# 4_viper_eagle_rep-periferals.net
KiCad netlist of a schematic drawn in Altium Designer
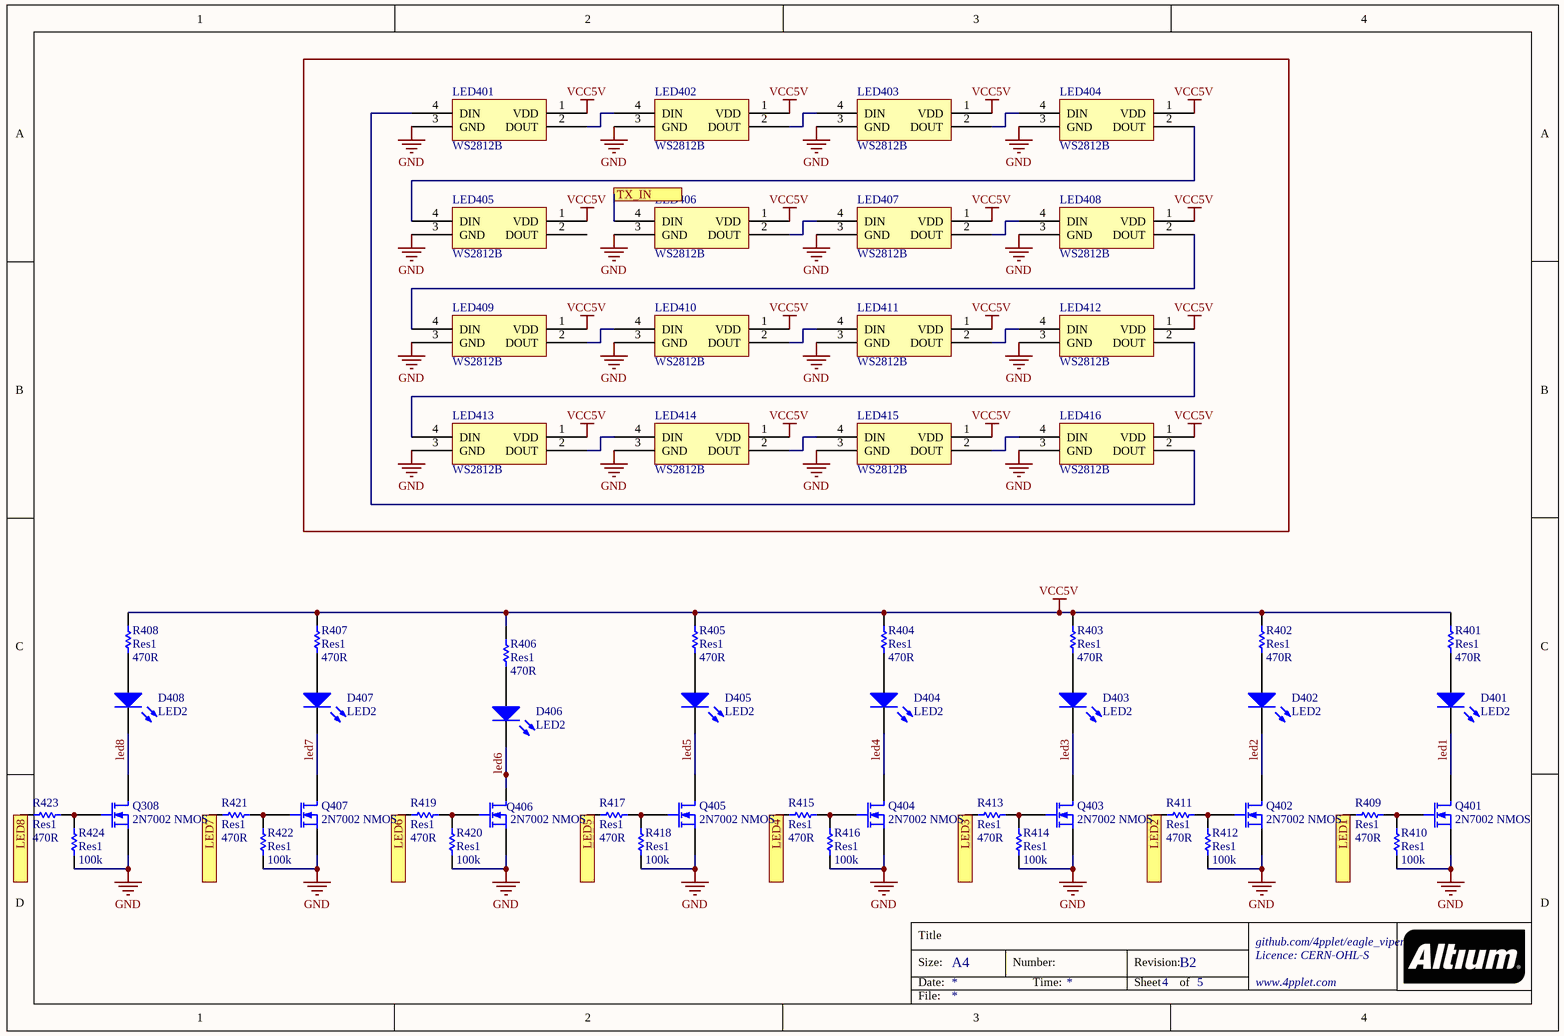
[diagram p0: 4_viper_eagle_rep-periferals.SchDoc]

(export (version "E")
  (design (tool "Eeschema 10.0.6"))
  (components
    (comp (ref "D401")
      (value "LED2")
      (footprint "LED - THT")
      (description "Typical RED, GREEN, YELLOW, AMBER GaAs LED")
      (libsource (lib "Miscellaneous Devices") (part "LED2"))
    )
    (comp (ref "D402")
      (value "LED2")
      (footprint "LED - THT")
      (description "Typical RED, GREEN, YELLOW, AMBER GaAs LED")
      (libsource (lib "Miscellaneous Devices") (part "LED2"))
    )
    (comp (ref "D403")
      (value "LED2")
      (footprint "LED - THT")
      (description "Typical RED, GREEN, YELLOW, AMBER GaAs LED")
      (libsource (lib "Miscellaneous Devices") (part "LED2"))
    )
    (comp (ref "D404")
      (value "LED2")
      (footprint "LED - THT")
      (description "Typical RED, GREEN, YELLOW, AMBER GaAs LED")
      (libsource (lib "Miscellaneous Devices") (part "LED2"))
    )
    (comp (ref "D405")
      (value "LED2")
      (footprint "LED - THT")
      (description "Typical RED, GREEN, YELLOW, AMBER GaAs LED")
      (libsource (lib "Miscellaneous Devices") (part "LED2"))
    )
    (comp (ref "D406")
      (value "LED2")
      (footprint "LED - THT")
      (description "Typical RED, GREEN, YELLOW, AMBER GaAs LED")
      (libsource (lib "Miscellaneous Devices") (part "LED2"))
    )
    (comp (ref "D407")
      (value "LED2")
      (footprint "LED - THT")
      (description "Typical RED, GREEN, YELLOW, AMBER GaAs LED")
      (libsource (lib "Miscellaneous Devices") (part "LED2"))
    )
    (comp (ref "D408")
      (value "LED2")
      (footprint "LED - THT")
      (description "Typical RED, GREEN, YELLOW, AMBER GaAs LED")
      (libsource (lib "Miscellaneous Devices") (part "LED2"))
    )
    (comp (ref "LED401")
      (value "WS2812B")
      (footprint "WS2812B")
      (fields (field (name "LCSC PART #") "C2874885") (field (name "MRF.PART") "WS2812B-V5/W"))
      (libsource (lib "Keebs") (part "WS2812B"))
    )
    (comp (ref "LED402")
      (value "WS2812B")
      (footprint "WS2812B")
      (fields (field (name "LCSC PART #") "C2874885") (field (name "MRF.PART") "WS2812B-V5/W"))
      (libsource (lib "Keebs") (part "WS2812B"))
    )
    (comp (ref "LED403")
      (value "WS2812B")
      (footprint "WS2812B")
      (fields (field (name "LCSC PART #") "C2874885") (field (name "MRF.PART") "WS2812B-V5/W"))
      (libsource (lib "Keebs") (part "WS2812B"))
    )
    (comp (ref "LED404")
      (value "WS2812B")
      (footprint "WS2812B")
      (fields (field (name "LCSC PART #") "C2874885") (field (name "MRF.PART") "WS2812B-V5/W"))
      (libsource (lib "Keebs") (part "WS2812B"))
    )
    (comp (ref "LED405")
      (value "WS2812B")
      (footprint "WS2812B")
      (fields (field (name "LCSC PART #") "C2874885") (field (name "MRF.PART") "WS2812B-V5/W"))
      (libsource (lib "Keebs") (part "WS2812B"))
    )
    (comp (ref "LED406")
      (value "WS2812B")
      (footprint "WS2812B")
      (fields (field (name "LCSC PART #") "C2874885") (field (name "MRF.PART") "WS2812B-V5/W"))
      (libsource (lib "Keebs") (part "WS2812B"))
    )
    (comp (ref "LED407")
      (value "WS2812B")
      (footprint "WS2812B")
      (fields (field (name "LCSC PART #") "C2874885") (field (name "MRF.PART") "WS2812B-V5/W"))
      (libsource (lib "Keebs") (part "WS2812B"))
    )
    (comp (ref "LED408")
      (value "WS2812B")
      (footprint "WS2812B")
      (fields (field (name "LCSC PART #") "C2874885") (field (name "MRF.PART") "WS2812B-V5/W"))
      (libsource (lib "Keebs") (part "WS2812B"))
    )
    (comp (ref "LED409")
      (value "WS2812B")
      (footprint "WS2812B")
      (fields (field (name "LCSC PART #") "C2874885") (field (name "MRF.PART") "WS2812B-V5/W"))
      (libsource (lib "Keebs") (part "WS2812B"))
    )
    (comp (ref "LED410")
      (value "WS2812B")
      (footprint "WS2812B")
      (fields (field (name "LCSC PART #") "C2874885") (field (name "MRF.PART") "WS2812B-V5/W"))
      (libsource (lib "Keebs") (part "WS2812B"))
    )
    (comp (ref "LED411")
      (value "WS2812B")
      (footprint "WS2812B")
      (fields (field (name "LCSC PART #") "C2874885") (field (name "MRF.PART") "WS2812B-V5/W"))
      (libsource (lib "Keebs") (part "WS2812B"))
    )
    (comp (ref "LED412")
      (value "WS2812B")
      (footprint "WS2812B")
      (fields (field (name "LCSC PART #") "C2874885") (field (name "MRF.PART") "WS2812B-V5/W"))
      (libsource (lib "Keebs") (part "WS2812B"))
    )
    (comp (ref "LED413")
      (value "WS2812B")
      (footprint "WS2812B")
      (fields (field (name "LCSC PART #") "C2874885") (field (name "MRF.PART") "WS2812B-V5/W"))
      (libsource (lib "Keebs") (part "WS2812B"))
    )
    (comp (ref "LED414")
      (value "WS2812B")
      (footprint "WS2812B")
      (fields (field (name "LCSC PART #") "C2874885") (field (name "MRF.PART") "WS2812B-V5/W"))
      (libsource (lib "Keebs") (part "WS2812B"))
    )
    (comp (ref "LED415")
      (value "WS2812B")
      (footprint "WS2812B")
      (fields (field (name "LCSC PART #") "C2874885") (field (name "MRF.PART") "WS2812B-V5/W"))
      (libsource (lib "Keebs") (part "WS2812B"))
    )
    (comp (ref "LED416")
      (value "WS2812B")
      (footprint "WS2812B")
      (fields (field (name "LCSC PART #") "C2874885") (field (name "MRF.PART") "WS2812B-V5/W"))
      (libsource (lib "Keebs") (part "WS2812B"))
    )
    (comp (ref "Q308")
      (value "2N7002 NMOS")
      (footprint "SOT-23-3")
      (description "N-Channel MOSFET")
      (fields (field (name "LCSC PART #") "C8545") (field (name "MRF.PART") "2N7002"))
      (libsource (lib "Miscellaneous Devices") (part "MOSFET-N"))
    )
    (comp (ref "Q401")
      (value "2N7002 NMOS")
      (footprint "SOT-23-3")
      (description "N-Channel MOSFET")
      (fields (field (name "LCSC PART #") "C8545") (field (name "MRF.PART") "2N7002"))
      (libsource (lib "Miscellaneous Devices") (part "MOSFET-N"))
    )
    (comp (ref "Q402")
      (value "2N7002 NMOS")
      (footprint "SOT-23-3")
      (description "N-Channel MOSFET")
      (fields (field (name "LCSC PART #") "C8545") (field (name "MRF.PART") "2N7002"))
      (libsource (lib "Miscellaneous Devices") (part "MOSFET-N"))
    )
    (comp (ref "Q403")
      (value "2N7002 NMOS")
      (footprint "SOT-23-3")
      (description "N-Channel MOSFET")
      (fields (field (name "LCSC PART #") "C8545") (field (name "MRF.PART") "2N7002"))
      (libsource (lib "Miscellaneous Devices") (part "MOSFET-N"))
    )
    (comp (ref "Q404")
      (value "2N7002 NMOS")
      (footprint "SOT-23-3")
      (description "N-Channel MOSFET")
      (fields (field (name "LCSC PART #") "C8545") (field (name "MRF.PART") "2N7002"))
      (libsource (lib "Miscellaneous Devices") (part "MOSFET-N"))
    )
    (comp (ref "Q405")
      (value "2N7002 NMOS")
      (footprint "SOT-23-3")
      (description "N-Channel MOSFET")
      (fields (field (name "LCSC PART #") "C8545") (field (name "MRF.PART") "2N7002"))
      (libsource (lib "Miscellaneous Devices") (part "MOSFET-N"))
    )
    (comp (ref "Q406")
      (value "2N7002 NMOS")
      (footprint "SOT-23-3")
      (description "N-Channel MOSFET")
      (fields (field (name "LCSC PART #") "C8545") (field (name "MRF.PART") "2N7002"))
      (libsource (lib "Miscellaneous Devices") (part "MOSFET-N"))
    )
    (comp (ref "Q407")
      (value "2N7002 NMOS")
      (footprint "SOT-23-3")
      (description "N-Channel MOSFET")
      (fields (field (name "LCSC PART #") "C8545") (field (name "MRF.PART") "2N7002"))
      (libsource (lib "Miscellaneous Devices") (part "MOSFET-N"))
    )
    (comp (ref "R401")
      (value "Res1")
      (footprint "R0603[1608]")
      (description "Resistor")
      (fields
        (field (name "ALTIUM_VALUE") "470R")
        (field (name "LCSC PART #") "C23179")
        (field (name "MRF.PART") "0603WAF4700T5E")
      )
      (libsource (lib "Miscellaneous Devices") (part "Res1"))
    )
    (comp (ref "R402")
      (value "Res1")
      (footprint "R0603[1608]")
      (description "Resistor")
      (fields
        (field (name "ALTIUM_VALUE") "470R")
        (field (name "LCSC PART #") "C23179")
        (field (name "MRF.PART") "0603WAF4700T5E")
      )
      (libsource (lib "Miscellaneous Devices") (part "Res1"))
    )
    (comp (ref "R403")
      (value "Res1")
      (footprint "R0603[1608]")
      (description "Resistor")
      (fields
        (field (name "ALTIUM_VALUE") "470R")
        (field (name "LCSC PART #") "C23179")
        (field (name "MRF.PART") "0603WAF4700T5E")
      )
      (libsource (lib "Miscellaneous Devices") (part "Res1"))
    )
    (comp (ref "R404")
      (value "Res1")
      (footprint "R0603[1608]")
      (description "Resistor")
      (fields
        (field (name "ALTIUM_VALUE") "470R")
        (field (name "LCSC PART #") "C23179")
        (field (name "MRF.PART") "0603WAF4700T5E")
      )
      (libsource (lib "Miscellaneous Devices") (part "Res1"))
    )
    (comp (ref "R405")
      (value "Res1")
      (footprint "R0603[1608]")
      (description "Resistor")
      (fields
        (field (name "ALTIUM_VALUE") "470R")
        (field (name "LCSC PART #") "C23179")
        (field (name "MRF.PART") "0603WAF4700T5E")
      )
      (libsource (lib "Miscellaneous Devices") (part "Res1"))
    )
    (comp (ref "R406")
      (value "Res1")
      (footprint "R0603[1608]")
      (description "Resistor")
      (fields
        (field (name "ALTIUM_VALUE") "470R")
        (field (name "LCSC PART #") "C23179")
        (field (name "MRF.PART") "0603WAF4700T5E")
      )
      (libsource (lib "Miscellaneous Devices") (part "Res1"))
    )
    (comp (ref "R407")
      (value "Res1")
      (footprint "R0603[1608]")
      (description "Resistor")
      (fields
        (field (name "ALTIUM_VALUE") "470R")
        (field (name "LCSC PART #") "C23179")
        (field (name "MRF.PART") "0603WAF4700T5E")
      )
      (libsource (lib "Miscellaneous Devices") (part "Res1"))
    )
    (comp (ref "R408")
      (value "Res1")
      (footprint "R0603[1608]")
      (description "Resistor")
      (fields
        (field (name "ALTIUM_VALUE") "470R")
        (field (name "LCSC PART #") "C23179")
        (field (name "MRF.PART") "0603WAF4700T5E")
      )
      (libsource (lib "Miscellaneous Devices") (part "Res1"))
    )
    (comp (ref "R409")
      (value "Res1")
      (footprint "R0603[1608]")
      (description "Resistor")
      (fields
        (field (name "ALTIUM_VALUE") "470R")
        (field (name "LCSC PART #") "C23179")
        (field (name "MRF.PART") "0603WAF4700T5E")
      )
      (libsource (lib "Miscellaneous Devices") (part "Res1"))
    )
    (comp (ref "R410")
      (value "Res1")
      (footprint "R0603[1608]")
      (description "Resistor")
      (fields
        (field (name "ALTIUM_VALUE") "100k")
        (field (name "MRF.PART") "0603WAF1003T5E")
        (field (name "LCSC PART #") "C25803")
      )
      (libsource (lib "Miscellaneous Devices") (part "Res1"))
    )
    (comp (ref "R411")
      (value "Res1")
      (footprint "R0603[1608]")
      (description "Resistor")
      (fields
        (field (name "ALTIUM_VALUE") "470R")
        (field (name "LCSC PART #") "C23179")
        (field (name "MRF.PART") "0603WAF4700T5E")
      )
      (libsource (lib "Miscellaneous Devices") (part "Res1"))
    )
    (comp (ref "R412")
      (value "Res1")
      (footprint "R0603[1608]")
      (description "Resistor")
      (fields
        (field (name "ALTIUM_VALUE") "100k")
        (field (name "MRF.PART") "0603WAF1003T5E")
        (field (name "LCSC PART #") "C25803")
      )
      (libsource (lib "Miscellaneous Devices") (part "Res1"))
    )
    (comp (ref "R413")
      (value "Res1")
      (footprint "R0603[1608]")
      (description "Resistor")
      (fields
        (field (name "ALTIUM_VALUE") "470R")
        (field (name "LCSC PART #") "C23179")
        (field (name "MRF.PART") "0603WAF4700T5E")
      )
      (libsource (lib "Miscellaneous Devices") (part "Res1"))
    )
    (comp (ref "R414")
      (value "Res1")
      (footprint "R0603[1608]")
      (description "Resistor")
      (fields
        (field (name "ALTIUM_VALUE") "100k")
        (field (name "MRF.PART") "0603WAF1003T5E")
        (field (name "LCSC PART #") "C25803")
      )
      (libsource (lib "Miscellaneous Devices") (part "Res1"))
    )
    (comp (ref "R415")
      (value "Res1")
      (footprint "R0603[1608]")
      (description "Resistor")
      (fields
        (field (name "ALTIUM_VALUE") "470R")
        (field (name "LCSC PART #") "C23179")
        (field (name "MRF.PART") "0603WAF4700T5E")
      )
      (libsource (lib "Miscellaneous Devices") (part "Res1"))
    )
    (comp (ref "R416")
      (value "Res1")
      (footprint "R0603[1608]")
      (description "Resistor")
      (fields
        (field (name "ALTIUM_VALUE") "100k")
        (field (name "MRF.PART") "0603WAF1003T5E")
        (field (name "LCSC PART #") "C25803")
      )
      (libsource (lib "Miscellaneous Devices") (part "Res1"))
    )
    (comp (ref "R417")
      (value "Res1")
      (footprint "R0603[1608]")
      (description "Resistor")
      (fields
        (field (name "ALTIUM_VALUE") "470R")
        (field (name "LCSC PART #") "C23179")
        (field (name "MRF.PART") "0603WAF4700T5E")
      )
      (libsource (lib "Miscellaneous Devices") (part "Res1"))
    )
    (comp (ref "R418")
      (value "Res1")
      (footprint "R0603[1608]")
      (description "Resistor")
      (fields
        (field (name "ALTIUM_VALUE") "100k")
        (field (name "MRF.PART") "0603WAF1003T5E")
        (field (name "LCSC PART #") "C25803")
      )
      (libsource (lib "Miscellaneous Devices") (part "Res1"))
    )
    (comp (ref "R419")
      (value "Res1")
      (footprint "R0603[1608]")
      (description "Resistor")
      (fields
        (field (name "ALTIUM_VALUE") "470R")
        (field (name "LCSC PART #") "C23179")
        (field (name "MRF.PART") "0603WAF4700T5E")
      )
      (libsource (lib "Miscellaneous Devices") (part "Res1"))
    )
    (comp (ref "R420")
      (value "Res1")
      (footprint "R0603[1608]")
      (description "Resistor")
      (fields
        (field (name "ALTIUM_VALUE") "100k")
        (field (name "MRF.PART") "0603WAF1003T5E")
        (field (name "LCSC PART #") "C25803")
      )
      (libsource (lib "Miscellaneous Devices") (part "Res1"))
    )
    (comp (ref "R421")
      (value "Res1")
      (footprint "R0603[1608]")
      (description "Resistor")
      (fields
        (field (name "ALTIUM_VALUE") "470R")
        (field (name "LCSC PART #") "C23179")
        (field (name "MRF.PART") "0603WAF4700T5E")
      )
      (libsource (lib "Miscellaneous Devices") (part "Res1"))
    )
    (comp (ref "R422")
      (value "Res1")
      (footprint "R0603[1608]")
      (description "Resistor")
      (fields
        (field (name "ALTIUM_VALUE") "100k")
        (field (name "MRF.PART") "0603WAF1003T5E")
        (field (name "LCSC PART #") "C25803")
      )
      (libsource (lib "Miscellaneous Devices") (part "Res1"))
    )
    (comp (ref "R423")
      (value "Res1")
      (footprint "R0603[1608]")
      (description "Resistor")
      (fields
        (field (name "ALTIUM_VALUE") "470R")
        (field (name "LCSC PART #") "C23179")
        (field (name "MRF.PART") "0603WAF4700T5E")
      )
      (libsource (lib "Miscellaneous Devices") (part "Res1"))
    )
    (comp (ref "R424")
      (value "Res1")
      (footprint "R0603[1608]")
      (description "Resistor")
      (fields
        (field (name "ALTIUM_VALUE") "100k")
        (field (name "MRF.PART") "0603WAF1003T5E")
        (field (name "LCSC PART #") "C25803")
      )
      (libsource (lib "Miscellaneous Devices") (part "Res1"))
    )
  )
  (nets
    (net (code "1") (name "/LED1") (class "Default")
      (node (ref "R409") (pin "1") (pinfunction "1_1") (pintype "passive"))
    )
    (net (code "2") (name "/LED2") (class "Default")
      (node (ref "R411") (pin "1") (pinfunction "1_1") (pintype "passive"))
    )
    (net (code "3") (name "/LED3") (class "Default")
      (node (ref "R413") (pin "1") (pinfunction "1_1") (pintype "passive"))
    )
    (net (code "4") (name "/LED4") (class "Default")
      (node (ref "R415") (pin "1") (pinfunction "1_1") (pintype "passive"))
    )
    (net (code "5") (name "/LED5") (class "Default")
      (node (ref "R417") (pin "1") (pinfunction "1_1") (pintype "passive"))
    )
    (net (code "6") (name "/LED6") (class "Default")
      (node (ref "R419") (pin "1") (pinfunction "1_1") (pintype "passive"))
    )
    (net (code "7") (name "/LED7") (class "Default")
      (node (ref "R421") (pin "1") (pinfunction "1_1") (pintype "passive"))
    )
    (net (code "8") (name "/LED8") (class "Default")
      (node (ref "R423") (pin "1") (pinfunction "1_1") (pintype "passive"))
    )
    (net (code "9") (name "/TX_IN") (class "Default")
      (node (ref "LED406") (pin "4") (pinfunction "DIN_4") (pintype "passive"))
    )
    (net (code "10") (name "/led1") (class "Default")
      (node (ref "D401") (pin "2") (pinfunction "K_2") (pintype "passive"))
      (node (ref "Q401") (pin "3") (pinfunction "D_3") (pintype "passive"))
    )
    (net (code "11") (name "/led2") (class "Default")
      (node (ref "D402") (pin "2") (pinfunction "K_2") (pintype "passive"))
      (node (ref "Q402") (pin "3") (pinfunction "D_3") (pintype "passive"))
    )
    (net (code "12") (name "/led3") (class "Default")
      (node (ref "D403") (pin "2") (pinfunction "K_2") (pintype "passive"))
      (node (ref "Q403") (pin "3") (pinfunction "D_3") (pintype "passive"))
    )
    (net (code "13") (name "/led4") (class "Default")
      (node (ref "D404") (pin "2") (pinfunction "K_2") (pintype "passive"))
      (node (ref "Q404") (pin "3") (pinfunction "D_3") (pintype "passive"))
    )
    (net (code "14") (name "/led5") (class "Default")
      (node (ref "D405") (pin "2") (pinfunction "K_2") (pintype "passive"))
      (node (ref "Q405") (pin "3") (pinfunction "D_3") (pintype "passive"))
    )
    (net (code "15") (name "/led6") (class "Default")
      (node (ref "D406") (pin "2") (pinfunction "K_2") (pintype "passive"))
      (node (ref "Q406") (pin "3") (pinfunction "D_3") (pintype "passive"))
    )
    (net (code "16") (name "/led7") (class "Default")
      (node (ref "D407") (pin "2") (pinfunction "K_2") (pintype "passive"))
      (node (ref "Q407") (pin "3") (pinfunction "D_3") (pintype "passive"))
    )
    (net (code "17") (name "/led8") (class "Default")
      (node (ref "D408") (pin "2") (pinfunction "K_2") (pintype "passive"))
      (node (ref "Q308") (pin "3") (pinfunction "D_3") (pintype "passive"))
    )
    (net (code "18") (name "GND") (class "Default")
      (node (ref "LED401") (pin "3") (pinfunction "GND_3") (pintype "passive"))
      (node (ref "LED402") (pin "3") (pinfunction "GND_3") (pintype "passive"))
      (node (ref "LED403") (pin "3") (pinfunction "GND_3") (pintype "passive"))
      (node (ref "LED404") (pin "3") (pinfunction "GND_3") (pintype "passive"))
      (node (ref "LED405") (pin "3") (pinfunction "GND_3") (pintype "passive"))
      (node (ref "LED406") (pin "3") (pinfunction "GND_3") (pintype "passive"))
      (node (ref "LED407") (pin "3") (pinfunction "GND_3") (pintype "passive"))
      (node (ref "LED408") (pin "3") (pinfunction "GND_3") (pintype "passive"))
      (node (ref "LED409") (pin "3") (pinfunction "GND_3") (pintype "passive"))
      (node (ref "LED410") (pin "3") (pinfunction "GND_3") (pintype "passive"))
      (node (ref "LED411") (pin "3") (pinfunction "GND_3") (pintype "passive"))
      (node (ref "LED412") (pin "3") (pinfunction "GND_3") (pintype "passive"))
      (node (ref "LED413") (pin "3") (pinfunction "GND_3") (pintype "passive"))
      (node (ref "LED414") (pin "3") (pinfunction "GND_3") (pintype "passive"))
      (node (ref "LED415") (pin "3") (pinfunction "GND_3") (pintype "passive"))
      (node (ref "LED416") (pin "3") (pinfunction "GND_3") (pintype "passive"))
      (node (ref "Q308") (pin "2") (pinfunction "S_2") (pintype "passive"))
      (node (ref "Q401") (pin "2") (pinfunction "S_2") (pintype "passive"))
      (node (ref "Q402") (pin "2") (pinfunction "S_2") (pintype "passive"))
      (node (ref "Q403") (pin "2") (pinfunction "S_2") (pintype "passive"))
      (node (ref "Q404") (pin "2") (pinfunction "S_2") (pintype "passive"))
      (node (ref "Q405") (pin "2") (pinfunction "S_2") (pintype "passive"))
      (node (ref "Q406") (pin "2") (pinfunction "S_2") (pintype "passive"))
      (node (ref "Q407") (pin "2") (pinfunction "S_2") (pintype "passive"))
      (node (ref "R410") (pin "2") (pinfunction "2_2") (pintype "passive"))
      (node (ref "R412") (pin "2") (pinfunction "2_2") (pintype "passive"))
      (node (ref "R414") (pin "2") (pinfunction "2_2") (pintype "passive"))
      (node (ref "R416") (pin "2") (pinfunction "2_2") (pintype "passive"))
      (node (ref "R418") (pin "2") (pinfunction "2_2") (pintype "passive"))
      (node (ref "R420") (pin "2") (pinfunction "2_2") (pintype "passive"))
      (node (ref "R422") (pin "2") (pinfunction "2_2") (pintype "passive"))
      (node (ref "R424") (pin "2") (pinfunction "2_2") (pintype "passive"))
    )
    (net (code "19") (name "Net-(D401-A)") (class "Default")
      (node (ref "D401") (pin "1") (pinfunction "A_1") (pintype "passive"))
      (node (ref "R401") (pin "2") (pinfunction "2_2") (pintype "passive"))
    )
    (net (code "20") (name "Net-(D402-A)") (class "Default")
      (node (ref "D402") (pin "1") (pinfunction "A_1") (pintype "passive"))
      (node (ref "R402") (pin "2") (pinfunction "2_2") (pintype "passive"))
    )
    (net (code "21") (name "Net-(D403-A)") (class "Default")
      (node (ref "D403") (pin "1") (pinfunction "A_1") (pintype "passive"))
      (node (ref "R403") (pin "2") (pinfunction "2_2") (pintype "passive"))
    )
    (net (code "22") (name "Net-(D404-A)") (class "Default")
      (node (ref "D404") (pin "1") (pinfunction "A_1") (pintype "passive"))
      (node (ref "R404") (pin "2") (pinfunction "2_2") (pintype "passive"))
    )
    (net (code "23") (name "Net-(D405-A)") (class "Default")
      (node (ref "D405") (pin "1") (pinfunction "A_1") (pintype "passive"))
      (node (ref "R405") (pin "2") (pinfunction "2_2") (pintype "passive"))
    )
    (net (code "24") (name "Net-(D406-A)") (class "Default")
      (node (ref "D406") (pin "1") (pinfunction "A_1") (pintype "passive"))
      (node (ref "R406") (pin "2") (pinfunction "2_2") (pintype "passive"))
    )
    (net (code "25") (name "Net-(D407-A)") (class "Default")
      (node (ref "D407") (pin "1") (pinfunction "A_1") (pintype "passive"))
      (node (ref "R407") (pin "2") (pinfunction "2_2") (pintype "passive"))
    )
    (net (code "26") (name "Net-(D408-A)") (class "Default")
      (node (ref "D408") (pin "1") (pinfunction "A_1") (pintype "passive"))
      (node (ref "R408") (pin "2") (pinfunction "2_2") (pintype "passive"))
    )
    (net (code "27") (name "Net-(LED401-DIN)") (class "Default")
      (node (ref "LED401") (pin "4") (pinfunction "DIN_4") (pintype "passive"))
      (node (ref "LED416") (pin "2") (pinfunction "DOUT_2") (pintype "passive"))
    )
    (net (code "28") (name "Net-(LED401-DOUT)") (class "Default")
      (node (ref "LED401") (pin "2") (pinfunction "DOUT_2") (pintype "passive"))
      (node (ref "LED402") (pin "4") (pinfunction "DIN_4") (pintype "passive"))
    )
    (net (code "29") (name "Net-(LED402-DOUT)") (class "Default")
      (node (ref "LED402") (pin "2") (pinfunction "DOUT_2") (pintype "passive"))
      (node (ref "LED403") (pin "4") (pinfunction "DIN_4") (pintype "passive"))
    )
    (net (code "30") (name "Net-(LED403-DOUT)") (class "Default")
      (node (ref "LED403") (pin "2") (pinfunction "DOUT_2") (pintype "passive"))
      (node (ref "LED404") (pin "4") (pinfunction "DIN_4") (pintype "passive"))
    )
    (net (code "31") (name "Net-(LED404-DOUT)") (class "Default")
      (node (ref "LED404") (pin "2") (pinfunction "DOUT_2") (pintype "passive"))
      (node (ref "LED405") (pin "4") (pinfunction "DIN_4") (pintype "passive"))
    )
    (net (code "32") (name "Net-(LED406-DOUT)") (class "Default")
      (node (ref "LED406") (pin "2") (pinfunction "DOUT_2") (pintype "passive"))
      (node (ref "LED407") (pin "4") (pinfunction "DIN_4") (pintype "passive"))
    )
    (net (code "33") (name "Net-(LED407-DOUT)") (class "Default")
      (node (ref "LED407") (pin "2") (pinfunction "DOUT_2") (pintype "passive"))
      (node (ref "LED408") (pin "4") (pinfunction "DIN_4") (pintype "passive"))
    )
    (net (code "34") (name "Net-(LED408-DOUT)") (class "Default")
      (node (ref "LED408") (pin "2") (pinfunction "DOUT_2") (pintype "passive"))
      (node (ref "LED409") (pin "4") (pinfunction "DIN_4") (pintype "passive"))
    )
    (net (code "35") (name "Net-(LED409-DOUT)") (class "Default")
      (node (ref "LED409") (pin "2") (pinfunction "DOUT_2") (pintype "passive"))
      (node (ref "LED410") (pin "4") (pinfunction "DIN_4") (pintype "passive"))
    )
    (net (code "36") (name "Net-(LED410-DOUT)") (class "Default")
      (node (ref "LED410") (pin "2") (pinfunction "DOUT_2") (pintype "passive"))
      (node (ref "LED411") (pin "4") (pinfunction "DIN_4") (pintype "passive"))
    )
    (net (code "37") (name "Net-(LED411-DOUT)") (class "Default")
      (node (ref "LED411") (pin "2") (pinfunction "DOUT_2") (pintype "passive"))
      (node (ref "LED412") (pin "4") (pinfunction "DIN_4") (pintype "passive"))
    )
    (net (code "38") (name "Net-(LED412-DOUT)") (class "Default")
      (node (ref "LED412") (pin "2") (pinfunction "DOUT_2") (pintype "passive"))
      (node (ref "LED413") (pin "4") (pinfunction "DIN_4") (pintype "passive"))
    )
    (net (code "39") (name "Net-(LED413-DOUT)") (class "Default")
      (node (ref "LED413") (pin "2") (pinfunction "DOUT_2") (pintype "passive"))
      (node (ref "LED414") (pin "4") (pinfunction "DIN_4") (pintype "passive"))
    )
    (net (code "40") (name "Net-(LED414-DOUT)") (class "Default")
      (node (ref "LED414") (pin "2") (pinfunction "DOUT_2") (pintype "passive"))
      (node (ref "LED415") (pin "4") (pinfunction "DIN_4") (pintype "passive"))
    )
    (net (code "41") (name "Net-(LED415-DOUT)") (class "Default")
      (node (ref "LED415") (pin "2") (pinfunction "DOUT_2") (pintype "passive"))
      (node (ref "LED416") (pin "4") (pinfunction "DIN_4") (pintype "passive"))
    )
    (net (code "42") (name "Net-(Q308-G)") (class "Default")
      (node (ref "Q308") (pin "1") (pinfunction "G_1") (pintype "passive"))
      (node (ref "R423") (pin "2") (pinfunction "2_2") (pintype "passive"))
      (node (ref "R424") (pin "1") (pinfunction "1_1") (pintype "passive"))
    )
    (net (code "43") (name "Net-(Q401-G)") (class "Default")
      (node (ref "Q401") (pin "1") (pinfunction "G_1") (pintype "passive"))
      (node (ref "R409") (pin "2") (pinfunction "2_2") (pintype "passive"))
      (node (ref "R410") (pin "1") (pinfunction "1_1") (pintype "passive"))
    )
    (net (code "44") (name "Net-(Q402-G)") (class "Default")
      (node (ref "Q402") (pin "1") (pinfunction "G_1") (pintype "passive"))
      (node (ref "R411") (pin "2") (pinfunction "2_2") (pintype "passive"))
      (node (ref "R412") (pin "1") (pinfunction "1_1") (pintype "passive"))
    )
    (net (code "45") (name "Net-(Q403-G)") (class "Default")
      (node (ref "Q403") (pin "1") (pinfunction "G_1") (pintype "passive"))
      (node (ref "R413") (pin "2") (pinfunction "2_2") (pintype "passive"))
      (node (ref "R414") (pin "1") (pinfunction "1_1") (pintype "passive"))
    )
    (net (code "46") (name "Net-(Q404-G)") (class "Default")
      (node (ref "Q404") (pin "1") (pinfunction "G_1") (pintype "passive"))
      (node (ref "R415") (pin "2") (pinfunction "2_2") (pintype "passive"))
      (node (ref "R416") (pin "1") (pinfunction "1_1") (pintype "passive"))
    )
    (net (code "47") (name "Net-(Q405-G)") (class "Default")
      (node (ref "Q405") (pin "1") (pinfunction "G_1") (pintype "passive"))
      (node (ref "R417") (pin "2") (pinfunction "2_2") (pintype "passive"))
      (node (ref "R418") (pin "1") (pinfunction "1_1") (pintype "passive"))
    )
    (net (code "48") (name "Net-(Q406-G)") (class "Default")
      (node (ref "Q406") (pin "1") (pinfunction "G_1") (pintype "passive"))
      (node (ref "R419") (pin "2") (pinfunction "2_2") (pintype "passive"))
      (node (ref "R420") (pin "1") (pinfunction "1_1") (pintype "passive"))
    )
    (net (code "49") (name "Net-(Q407-G)") (class "Default")
      (node (ref "Q407") (pin "1") (pinfunction "G_1") (pintype "passive"))
      (node (ref "R421") (pin "2") (pinfunction "2_2") (pintype "passive"))
      (node (ref "R422") (pin "1") (pinfunction "1_1") (pintype "passive"))
    )
    (net (code "50") (name "VCC5V") (class "Default")
      (node (ref "LED401") (pin "1") (pinfunction "VDD_1") (pintype "passive"))
      (node (ref "LED402") (pin "1") (pinfunction "VDD_1") (pintype "passive"))
      (node (ref "LED403") (pin "1") (pinfunction "VDD_1") (pintype "passive"))
      (node (ref "LED404") (pin "1") (pinfunction "VDD_1") (pintype "passive"))
      (node (ref "LED405") (pin "1") (pinfunction "VDD_1") (pintype "passive"))
      (node (ref "LED406") (pin "1") (pinfunction "VDD_1") (pintype "passive"))
      (node (ref "LED407") (pin "1") (pinfunction "VDD_1") (pintype "passive"))
      (node (ref "LED408") (pin "1") (pinfunction "VDD_1") (pintype "passive"))
      (node (ref "LED409") (pin "1") (pinfunction "VDD_1") (pintype "passive"))
      (node (ref "LED410") (pin "1") (pinfunction "VDD_1") (pintype "passive"))
      (node (ref "LED411") (pin "1") (pinfunction "VDD_1") (pintype "passive"))
      (node (ref "LED412") (pin "1") (pinfunction "VDD_1") (pintype "passive"))
      (node (ref "LED413") (pin "1") (pinfunction "VDD_1") (pintype "passive"))
      (node (ref "LED414") (pin "1") (pinfunction "VDD_1") (pintype "passive"))
      (node (ref "LED415") (pin "1") (pinfunction "VDD_1") (pintype "passive"))
      (node (ref "LED416") (pin "1") (pinfunction "VDD_1") (pintype "passive"))
      (node (ref "R401") (pin "1") (pinfunction "1_1") (pintype "passive"))
      (node (ref "R402") (pin "1") (pinfunction "1_1") (pintype "passive"))
      (node (ref "R403") (pin "1") (pinfunction "1_1") (pintype "passive"))
      (node (ref "R404") (pin "1") (pinfunction "1_1") (pintype "passive"))
      (node (ref "R405") (pin "1") (pinfunction "1_1") (pintype "passive"))
      (node (ref "R406") (pin "1") (pinfunction "1_1") (pintype "passive"))
      (node (ref "R407") (pin "1") (pinfunction "1_1") (pintype "passive"))
      (node (ref "R408") (pin "1") (pinfunction "1_1") (pintype "passive"))
    )
    (net (code "51") (name "unconnected-(LED405-DOUT-Pad2)") (class "Default")
      (node (ref "LED405") (pin "2") (pinfunction "DOUT_2") (pintype "passive"))
    )
  )
)
